# Watchdog.net
KiCad netlist of a schematic drawn in Altium Designer
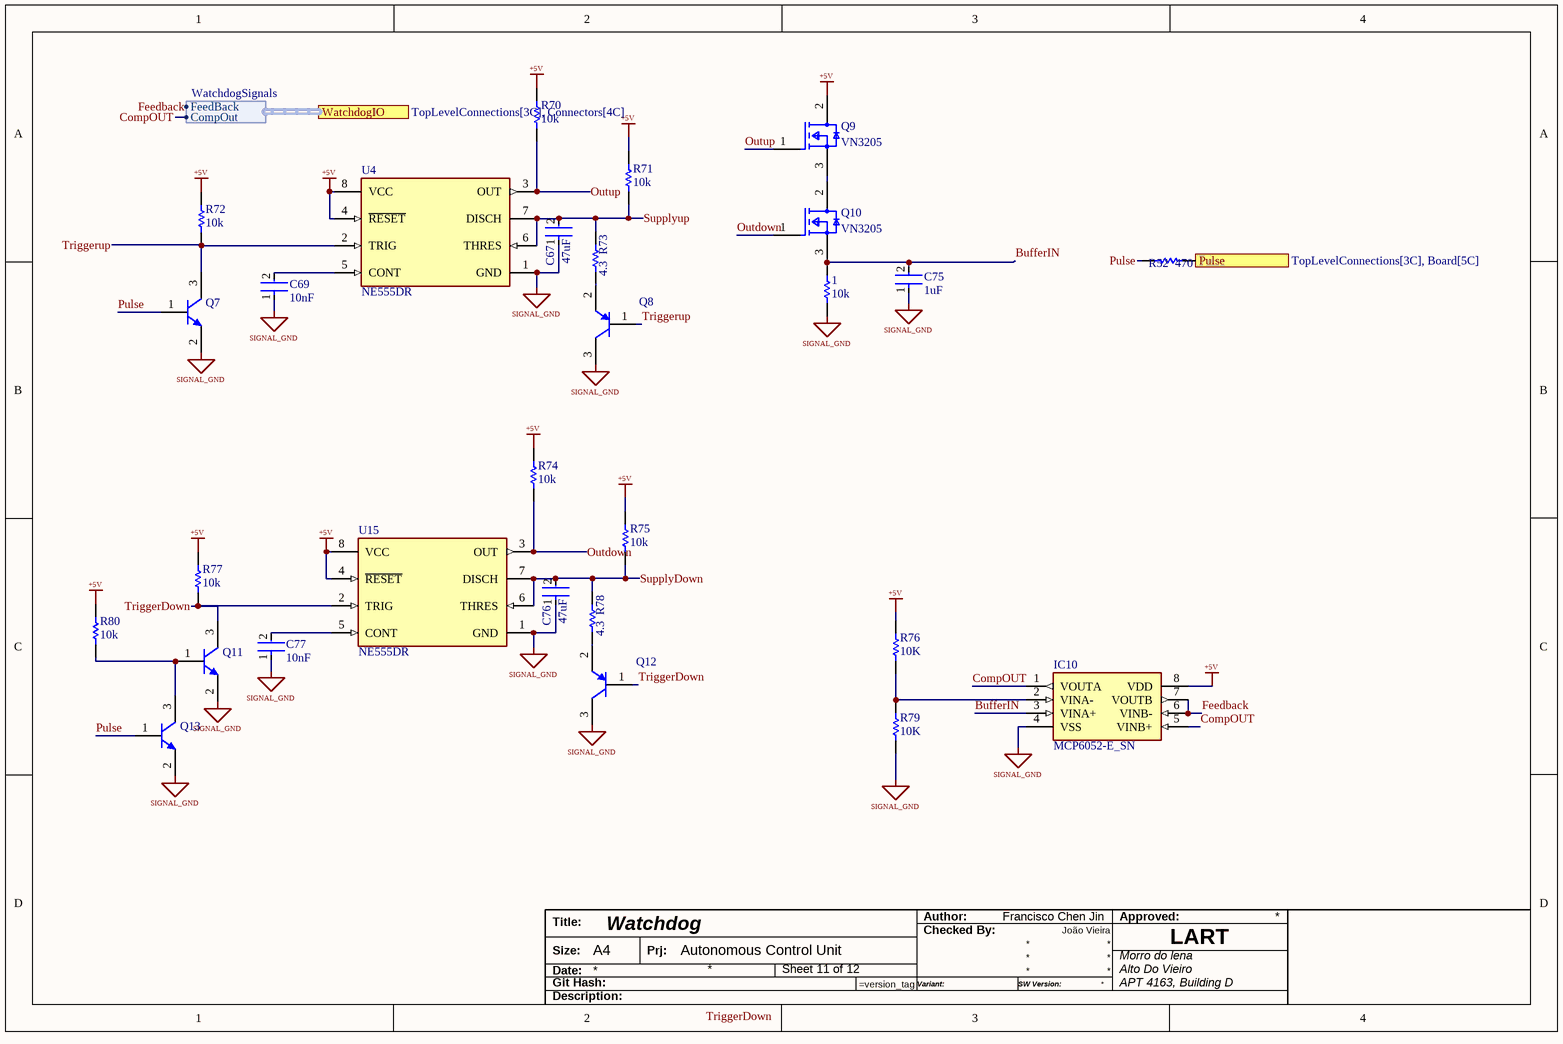
[diagram p0: Watchdog.SchDoc]

(export (version "E")
  (design (tool "Eeschema 10.0.6"))
  (components
    (comp (ref "1")
      (value "10k")
      (footprint "RESC2013X50X30LL20T20")
      (fields (field (name "MANUFACTURER") "Vishay Dale") (field (name "PART NUMBER") "CRCW08050000Z0EA"))
      (libsource (lib "Altium Content Vault") (part "RES"))
    )
    (comp (ref "C67")
      (value "47uF")
      (footprint "FP-0805-L_2_01_0_2-W_1_25-IPC_B")
      (description "General Purpose Ceramic Capacitor, 0805, 100pF, 1%, C0G, 30ppm/°C, 100V")
      (fields (field (name "TOLERANCE") "1%") (field (name "VOLTAGE") "100V"))
      (libsource (lib "Altium Content Vault") (part "02cd4be3c70576c341d710602a673aa"))
    )
    (comp (ref "C69")
      (value "10nF")
      (footprint "FP-0805-L_2_01_0_2-W_1_25-IPC_B")
      (description "General Purpose Ceramic Capacitor, 0805, 100pF, 1%, C0G, 30ppm/°C, 100V")
      (fields (field (name "TOLERANCE") "1%") (field (name "VOLTAGE") "100V"))
      (libsource (lib "Altium Content Vault") (part "02cd4be3c70576c341d710602a673aa"))
    )
    (comp (ref "C75")
      (value "1uF")
      (footprint "FP-0805-L_2_01_0_2-W_1_25-IPC_B")
      (description "General Purpose Ceramic Capacitor, 0805, 100pF, 1%, C0G, 30ppm/°C, 100V")
      (fields (field (name "TOLERANCE") "1%") (field (name "VOLTAGE") "100V"))
      (libsource (lib "Altium Content Vault") (part "02cd4be3c70576c341d710602a673aa"))
    )
    (comp (ref "C76")
      (value "47uF")
      (footprint "FP-0805-L_2_01_0_2-W_1_25-IPC_B")
      (description "General Purpose Ceramic Capacitor, 0805, 100pF, 1%, C0G, 30ppm/°C, 100V")
      (fields (field (name "TOLERANCE") "1%") (field (name "VOLTAGE") "100V"))
      (libsource (lib "Altium Content Vault") (part "02cd4be3c70576c341d710602a673aa"))
    )
    (comp (ref "C77")
      (value "10nF")
      (footprint "FP-0805-L_2_01_0_2-W_1_25-IPC_B")
      (description "General Purpose Ceramic Capacitor, 0805, 100pF, 1%, C0G, 30ppm/°C, 100V")
      (fields (field (name "TOLERANCE") "1%") (field (name "VOLTAGE") "100V"))
      (libsource (lib "Altium Content Vault") (part "02cd4be3c70576c341d710602a673aa"))
    )
    (comp (ref "IC10")
      (value "MCP6052-E_SN")
      (footprint "SOIC127P600X175-8N")
      (description "Integrated Circuit")
      (fields
        (field (name "MANUFACTURER_PART_NUMBER") "MCP6052-E/SN")
        (field (name "MOUSER PART NUMBER") "579-MCP6052-E/SN")
      )
      (libsource (lib "DesagoSch") (part "MCP6052-E_SN"))
    )
    (comp (ref "Q7")
      (value "MMBTA42LT1G")
      (footprint "ONSC-SOT-23-3-318-08_V")
      (description "High Voltage Transistor, NPN Silicon, 3-Pin SOT-23, Pb-Free, Tape and Reel")
      (fields (field (name "MANUFACTURER") "On Semiconductor"))
      (libsource (lib "Altium Content Vault") (part "ONSC-NPN-B1E2C3-3"))
    )
    (comp (ref "Q8")
      (value "MMBT4403LT1G")
      (footprint "ONSC-SOT-23-3-318-08_V")
      (description "Switching Transistor, PNP Silicon, 3-Pin SOT-23, Pb-Free, Tape and Reel")
      (fields (field (name "MANUFACTURER") "On Semiconductor"))
      (libsource (lib "Altium Content Vault") (part "ONSC-PNP-B1E2C3-3"))
    )
    (comp (ref "Q9")
      (value "VN3205")
      (footprint "FP-TN2510N8-G-IPC_C")
      (description "MOSFET N-CH 100V 730MA TO243AA")
      (libsource (lib "Altium Content Vault") (part "0c230b6be11ab2f8d79771084c6aa09"))
    )
    (comp (ref "Q10")
      (value "VN3205")
      (footprint "FP-TN2510N8-G-IPC_C")
      (description "MOSFET N-CH 100V 730MA TO243AA")
      (libsource (lib "Altium Content Vault") (part "0c230b6be11ab2f8d79771084c6aa09"))
    )
    (comp (ref "Q11")
      (value "MMBTA42LT1G")
      (footprint "ONSC-SOT-23-3-318-08_V")
      (description "High Voltage Transistor, NPN Silicon, 3-Pin SOT-23, Pb-Free, Tape and Reel")
      (fields (field (name "MANUFACTURER") "On Semiconductor"))
      (libsource (lib "Altium Content Vault") (part "ONSC-NPN-B1E2C3-3"))
    )
    (comp (ref "Q12")
      (value "MMBT4403LT1G")
      (footprint "ONSC-SOT-23-3-318-08_V")
      (description "Switching Transistor, PNP Silicon, 3-Pin SOT-23, Pb-Free, Tape and Reel")
      (fields (field (name "MANUFACTURER") "On Semiconductor"))
      (libsource (lib "Altium Content Vault") (part "ONSC-PNP-B1E2C3-3"))
    )
    (comp (ref "Q13")
      (value "MMBTA42LT1G")
      (footprint "ONSC-SOT-23-3-318-08_V")
      (description "High Voltage Transistor, NPN Silicon, 3-Pin SOT-23, Pb-Free, Tape and Reel")
      (fields (field (name "MANUFACTURER") "On Semiconductor"))
      (libsource (lib "Altium Content Vault") (part "ONSC-NPN-B1E2C3-3"))
    )
    (comp (ref "R52")
      (value "470")
      (footprint "RESC2013X50X30LL20T20")
      (fields (field (name "MANUFACTURER") "Vishay Dale") (field (name "PART NUMBER") "CRCW08050000Z0EA"))
      (libsource (lib "Altium Content Vault") (part "RES"))
    )
    (comp (ref "R70")
      (value "10k")
      (footprint "RESC2013X50X30LL20T20")
      (fields (field (name "MANUFACTURER") "Vishay Dale") (field (name "PART NUMBER") "CRCW08050000Z0EA"))
      (libsource (lib "Altium Content Vault") (part "RES"))
    )
    (comp (ref "R71")
      (value "10k")
      (footprint "RESC2013X50X30LL20T20")
      (fields (field (name "MANUFACTURER") "Vishay Dale") (field (name "PART NUMBER") "CRCW08050000Z0EA"))
      (libsource (lib "Altium Content Vault") (part "RES"))
    )
    (comp (ref "R72")
      (value "10k")
      (footprint "RESC2013X50X30LL20T20")
      (fields (field (name "MANUFACTURER") "Vishay Dale") (field (name "PART NUMBER") "CRCW08050000Z0EA"))
      (libsource (lib "Altium Content Vault") (part "RES"))
    )
    (comp (ref "R73")
      (value "4.3")
      (footprint "RESC2013X50X30LL20T20")
      (fields (field (name "MANUFACTURER") "Vishay Dale") (field (name "PART NUMBER") "CRCW08050000Z0EA"))
      (libsource (lib "Altium Content Vault") (part "RES"))
    )
    (comp (ref "R74")
      (value "10k")
      (footprint "RESC2013X50X30LL20T20")
      (fields (field (name "MANUFACTURER") "Vishay Dale") (field (name "PART NUMBER") "CRCW08050000Z0EA"))
      (libsource (lib "Altium Content Vault") (part "RES"))
    )
    (comp (ref "R75")
      (value "10k")
      (footprint "RESC2013X50X30LL20T20")
      (fields (field (name "MANUFACTURER") "Vishay Dale") (field (name "PART NUMBER") "CRCW08050000Z0EA"))
      (libsource (lib "Altium Content Vault") (part "RES"))
    )
    (comp (ref "R76")
      (value "10K")
      (footprint "RESC2013X50X30LL20T20")
      (fields (field (name "MANUFACTURER") "Vishay Dale") (field (name "PART NUMBER") "CRCW08050000Z0EA"))
      (libsource (lib "Altium Content Vault") (part "RES"))
    )
    (comp (ref "R77")
      (value "10k")
      (footprint "RESC2013X50X30LL20T20")
      (fields (field (name "MANUFACTURER") "Vishay Dale") (field (name "PART NUMBER") "CRCW08050000Z0EA"))
      (libsource (lib "Altium Content Vault") (part "RES"))
    )
    (comp (ref "R78")
      (value "4.3")
      (footprint "RESC2013X50X30LL20T20")
      (fields (field (name "MANUFACTURER") "Vishay Dale") (field (name "PART NUMBER") "CRCW08050000Z0EA"))
      (libsource (lib "Altium Content Vault") (part "RES"))
    )
    (comp (ref "R79")
      (value "10K")
      (footprint "RESC2013X50X30LL20T20")
      (fields (field (name "MANUFACTURER") "Vishay Dale") (field (name "PART NUMBER") "CRCW08050000Z0EA"))
      (libsource (lib "Altium Content Vault") (part "RES"))
    )
    (comp (ref "R80")
      (value "10k")
      (footprint "RESC2013X50X30LL20T20")
      (fields (field (name "MANUFACTURER") "Vishay Dale") (field (name "PART NUMBER") "CRCW08050000Z0EA"))
      (libsource (lib "Altium Content Vault") (part "RES"))
    )
    (comp (ref "U4")
      (value "NE555DR")
      (footprint "FP-D0008A-IPC_A")
      (description "IC OSC SGL TIMER 100KHZ 8-SOIC")
      (libsource (lib "Altium Content Vault") (part "a29bba90211dec1890110b94dad7d53"))
    )
    (comp (ref "U15")
      (value "NE555DR")
      (footprint "FP-D0008A-IPC_A")
      (description "IC OSC SGL TIMER 100KHZ 8-SOIC")
      (libsource (lib "Altium Content Vault") (part "a29bba90211dec1890110b94dad7d53"))
    )
  )
  (nets
    (net (code "2") (name "+5V") (class "Default")
      (node (ref "IC10") (pin "8") (pinfunction "VDD_8") (pintype "power_in"))
      (node (ref "Q9") (pin "2") (pinfunction "DRAIN_2") (pintype "passive"))
      (node (ref "R70") (pin "2") (pinfunction "2_2") (pintype "passive"))
      (node (ref "R71") (pin "1") (pinfunction "1_1") (pintype "passive"))
      (node (ref "R72") (pin "1") (pinfunction "1_1") (pintype "passive"))
      (node (ref "R74") (pin "2") (pinfunction "2_2") (pintype "passive"))
      (node (ref "R75") (pin "1") (pinfunction "1_1") (pintype "passive"))
      (node (ref "R76") (pin "1") (pinfunction "1_1") (pintype "passive"))
      (node (ref "R77") (pin "1") (pinfunction "1_1") (pintype "passive"))
      (node (ref "R80") (pin "1") (pinfunction "1_1") (pintype "passive"))
      (node (ref "U15") (pin "4") (pinfunction "~{RESET}_4") (pintype "input"))
      (node (ref "U15") (pin "8") (pinfunction "VCC_8") (pintype "power_in"))
      (node (ref "U4") (pin "4") (pinfunction "~{RESET}_4") (pintype "input"))
      (node (ref "U4") (pin "8") (pinfunction "VCC_8") (pintype "power_in"))
    )
    (net (code "3") (name "/BufferIN") (class "Default")
      (node (ref "1") (pin "2") (pinfunction "2_2") (pintype "passive"))
      (node (ref "C75") (pin "2") (pinfunction "2_2") (pintype "passive"))
      (node (ref "IC10") (pin "3") (pinfunction "VINA+_3") (pintype "input"))
      (node (ref "Q10") (pin "3") (pinfunction "SOURCE_3") (pintype "passive"))
    )
    (net (code "4") (name "/CompOUT") (class "Default")
      (node (ref "IC10") (pin "1") (pinfunction "VOUTA_1") (pintype "output"))
      (node (ref "IC10") (pin "5") (pinfunction "VINB+_5") (pintype "input"))
    )
    (net (code "5") (name "/Feedback") (class "Default")
      (node (ref "IC10") (pin "6") (pinfunction "VINB-_6") (pintype "input"))
      (node (ref "IC10") (pin "7") (pinfunction "VOUTB_7") (pintype "output"))
    )
    (net (code "6") (name "/Outdown") (class "Default")
      (node (ref "Q10") (pin "1") (pinfunction "GATE_1") (pintype "passive"))
      (node (ref "R74") (pin "1") (pinfunction "1_1") (pintype "passive"))
      (node (ref "U15") (pin "3") (pinfunction "OUT_3") (pintype "output"))
    )
    (net (code "7") (name "/Outup") (class "Default")
      (node (ref "Q9") (pin "1") (pinfunction "GATE_1") (pintype "passive"))
      (node (ref "R70") (pin "1") (pinfunction "1_1") (pintype "passive"))
      (node (ref "U4") (pin "3") (pinfunction "OUT_3") (pintype "output"))
    )
    (net (code "8") (name "/Pulse") (class "Default")
      (node (ref "Q13") (pin "1") (pinfunction "B_1") (pintype "passive"))
      (node (ref "Q7") (pin "1") (pinfunction "B_1") (pintype "passive"))
      (node (ref "R52") (pin "1") (pinfunction "1_1") (pintype "passive"))
    )
    (net (code "9") (name "/SupplyDown") (class "Default")
      (node (ref "C76") (pin "2") (pinfunction "2_2") (pintype "passive"))
      (node (ref "R75") (pin "2") (pinfunction "2_2") (pintype "passive"))
      (node (ref "R78") (pin "2") (pinfunction "2_2") (pintype "passive"))
      (node (ref "U15") (pin "6") (pinfunction "THRES_6") (pintype "input"))
      (node (ref "U15") (pin "7") (pinfunction "DISCH_7") (pintype "open_collector"))
    )
    (net (code "10") (name "/Supplyup") (class "Default")
      (node (ref "C67") (pin "2") (pinfunction "2_2") (pintype "passive"))
      (node (ref "R71") (pin "2") (pinfunction "2_2") (pintype "passive"))
      (node (ref "R73") (pin "2") (pinfunction "2_2") (pintype "passive"))
      (node (ref "U4") (pin "6") (pinfunction "THRES_6") (pintype "input"))
      (node (ref "U4") (pin "7") (pinfunction "DISCH_7") (pintype "open_collector"))
    )
    (net (code "11") (name "/TriggerDown") (class "Default")
      (node (ref "Q11") (pin "3") (pinfunction "C_3") (pintype "passive"))
      (node (ref "Q12") (pin "1") (pinfunction "B_1") (pintype "passive"))
      (node (ref "R77") (pin "2") (pinfunction "2_2") (pintype "passive"))
      (node (ref "U15") (pin "2") (pinfunction "TRIG_2") (pintype "input"))
    )
    (net (code "12") (name "/Triggerup") (class "Default")
      (node (ref "Q7") (pin "3") (pinfunction "C_3") (pintype "passive"))
      (node (ref "Q8") (pin "1") (pinfunction "B_1") (pintype "passive"))
      (node (ref "R72") (pin "2") (pinfunction "2_2") (pintype "passive"))
      (node (ref "U4") (pin "2") (pinfunction "TRIG_2") (pintype "input"))
    )
    (net (code "14") (name "Net-(IC10-VINA-)") (class "Default")
      (node (ref "IC10") (pin "2") (pinfunction "VINA-_2") (pintype "input"))
      (node (ref "R76") (pin "2") (pinfunction "2_2") (pintype "passive"))
      (node (ref "R79") (pin "1") (pinfunction "1_1") (pintype "passive"))
    )
    (net (code "15") (name "Net-(Q8-E)") (class "Default")
      (node (ref "Q8") (pin "2") (pinfunction "E_2") (pintype "passive"))
      (node (ref "R73") (pin "1") (pinfunction "1_1") (pintype "passive"))
    )
    (net (code "16") (name "Net-(Q10-DRAIN)") (class "Default")
      (node (ref "Q10") (pin "2") (pinfunction "DRAIN_2") (pintype "passive"))
      (node (ref "Q9") (pin "3") (pinfunction "SOURCE_3") (pintype "passive"))
    )
    (net (code "17") (name "Net-(Q11-B)") (class "Default")
      (node (ref "Q11") (pin "1") (pinfunction "B_1") (pintype "passive"))
      (node (ref "Q13") (pin "3") (pinfunction "C_3") (pintype "passive"))
      (node (ref "R80") (pin "2") (pinfunction "2_2") (pintype "passive"))
    )
    (net (code "18") (name "Net-(Q12-E)") (class "Default")
      (node (ref "Q12") (pin "2") (pinfunction "E_2") (pintype "passive"))
      (node (ref "R78") (pin "1") (pinfunction "1_1") (pintype "passive"))
    )
    (net (code "19") (name "Net-(U4-CONT)") (class "Default")
      (node (ref "C69") (pin "2") (pinfunction "2_2") (pintype "passive"))
      (node (ref "U4") (pin "5") (pinfunction "CONT_5") (pintype "input"))
    )
    (net (code "20") (name "Net-(U15-CONT)") (class "Default")
      (node (ref "C77") (pin "2") (pinfunction "2_2") (pintype "passive"))
      (node (ref "U15") (pin "5") (pinfunction "CONT_5") (pintype "input"))
    )
    (net (code "21") (name "SIGNAL_GND") (class "Default")
      (node (ref "1") (pin "1") (pinfunction "1_1") (pintype "passive"))
      (node (ref "C67") (pin "1") (pinfunction "1_1") (pintype "passive"))
      (node (ref "C69") (pin "1") (pinfunction "1_1") (pintype "passive"))
      (node (ref "C75") (pin "1") (pinfunction "1_1") (pintype "passive"))
      (node (ref "C76") (pin "1") (pinfunction "1_1") (pintype "passive"))
      (node (ref "C77") (pin "1") (pinfunction "1_1") (pintype "passive"))
      (node (ref "IC10") (pin "4") (pinfunction "VSS_4") (pintype "power_in"))
      (node (ref "Q11") (pin "2") (pinfunction "E_2") (pintype "passive"))
      (node (ref "Q12") (pin "3") (pinfunction "C_3") (pintype "passive"))
      (node (ref "Q13") (pin "2") (pinfunction "E_2") (pintype "passive"))
      (node (ref "Q7") (pin "2") (pinfunction "E_2") (pintype "passive"))
      (node (ref "Q8") (pin "3") (pinfunction "C_3") (pintype "passive"))
      (node (ref "R79") (pin "2") (pinfunction "2_2") (pintype "passive"))
      (node (ref "U15") (pin "1") (pinfunction "GND_1") (pintype "power_in"))
      (node (ref "U4") (pin "1") (pinfunction "GND_1") (pintype "power_in"))
    )
    (net (code "22") (name "unconnected-(R52-Pad2)") (class "Default")
      (node (ref "R52") (pin "2") (pinfunction "2_2") (pintype "passive"))
    )
  )
)
